# Main.net
KiCad netlist of a schematic drawn in EAGLE
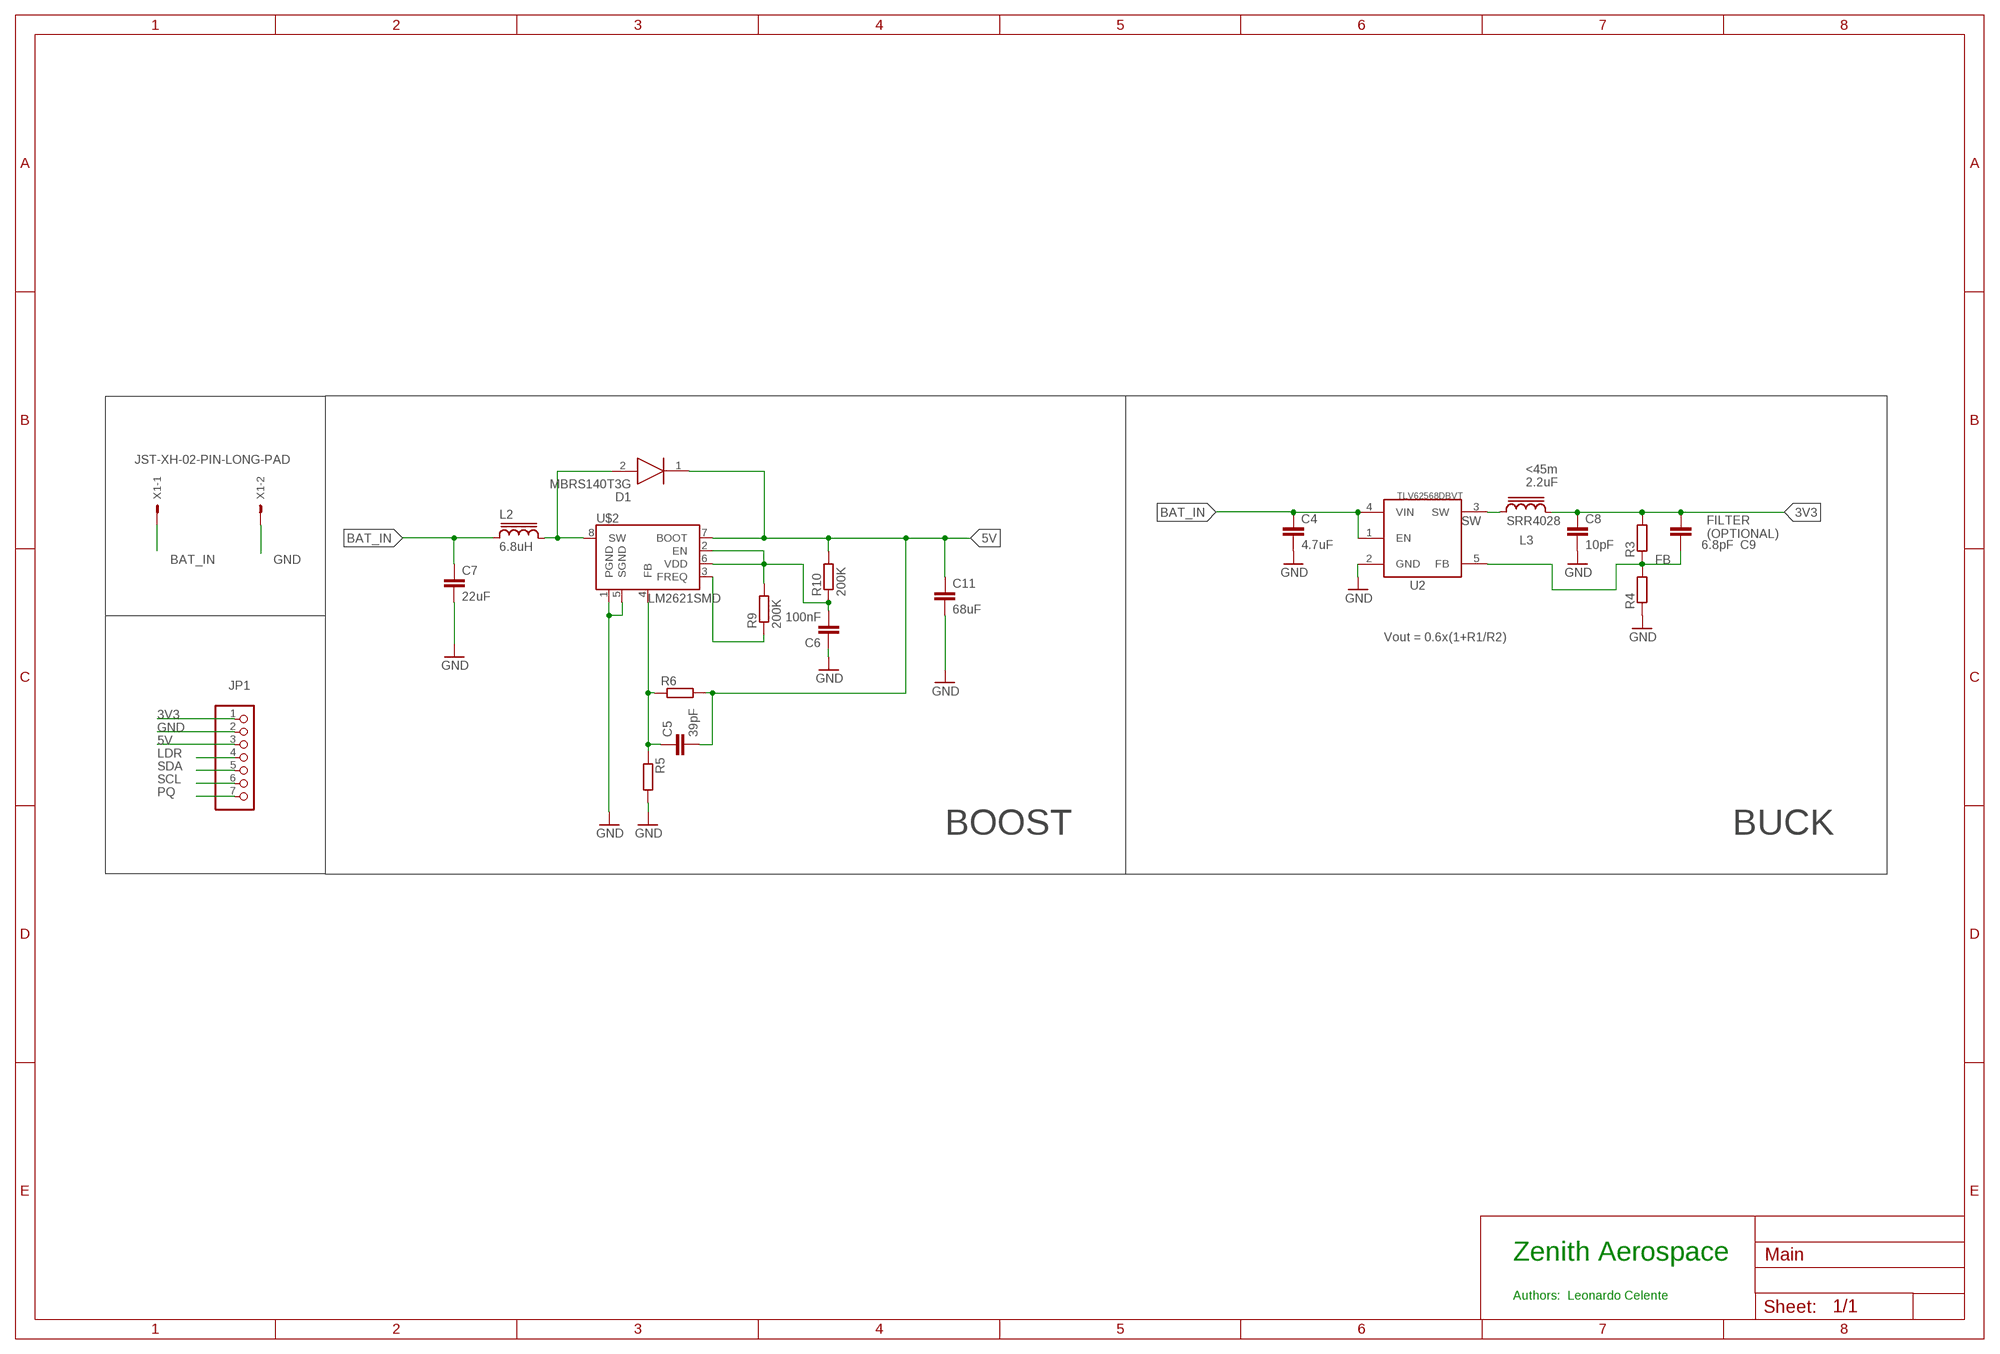
[diagram p0: schematic, sheet 1]

(export (version "E")
  (design (tool "Eeschema 10.0.6"))
  (components
    (comp (ref "C4")
      (value "4.7uF")
      (footprint "eagle-import:C0805")
      (libsource (lib "eagle-import") (part "C-EUC0805"))
    )
    (comp (ref "C5")
      (value "39pF")
      (footprint "eagle-import:C0805")
      (libsource (lib "eagle-import") (part "C-EUC0805"))
    )
    (comp (ref "C6")
      (value "100nF")
      (footprint "eagle-import:C0805")
      (libsource (lib "eagle-import") (part "C-EUC0805"))
    )
    (comp (ref "C7")
      (value "22uF")
      (footprint "eagle-import:C1210")
      (libsource (lib "eagle-import") (part "C-EUC1210"))
    )
    (comp (ref "C8")
      (value "10pF")
      (footprint "eagle-import:C0805")
      (libsource (lib "eagle-import") (part "C-EUC0805"))
    )
    (comp (ref "C9")
      (value "6.8pF")
      (footprint "eagle-import:C0805")
      (libsource (lib "eagle-import") (part "C-EUC0805"))
    )
    (comp (ref "C11")
      (value "68uF")
      (footprint "eagle-import:C1210")
      (libsource (lib "eagle-import") (part "C-EUC1210"))
    )
    (comp (ref "D1")
      (value "MBRS140T3G")
      (footprint "eagle-import:DIOM5436X247N")
      (fields (field (name "RS_PART_NUMBER") "5452074P"))
      (libsource (lib "eagle-import") (part "MBRS140T3G"))
    )
    (comp (ref "JP1")
      (value "PINHD-1X7")
      (footprint "eagle-import:1X07")
      (libsource (lib "eagle-import") (part "PINHD-1X7"))
    )
    (comp (ref "L2")
      (value "6.8uH")
      (footprint "eagle-import:SRR1280")
      (libsource (lib "eagle-import") (part "SRR1280"))
    )
    (comp (ref "L3")
      (value "SRR4028")
      (footprint "eagle-import:SRR4028")
      (fields (field (name "DCR") "<45m") (field (name "L") "2.2uF"))
      (libsource (lib "eagle-import") (part "SRR4028"))
    )
    (comp (ref "R3")
      (value "R-EU_R0805")
      (footprint "eagle-import:R0805")
      (libsource (lib "eagle-import") (part "R-EU_R0805"))
    )
    (comp (ref "R4")
      (value "R-EU_R0805")
      (footprint "eagle-import:R0805")
      (libsource (lib "eagle-import") (part "R-EU_R0805"))
    )
    (comp (ref "R5")
      (value "R-EU_R0805")
      (footprint "eagle-import:R0805")
      (libsource (lib "eagle-import") (part "R-EU_R0805"))
    )
    (comp (ref "R6")
      (value "R-EU_R0805")
      (footprint "eagle-import:R0805")
      (libsource (lib "eagle-import") (part "R-EU_R0805"))
    )
    (comp (ref "R9")
      (value "200K")
      (footprint "eagle-import:R0805")
      (libsource (lib "eagle-import") (part "R-EU_R0805"))
    )
    (comp (ref "R10")
      (value "200K")
      (footprint "eagle-import:R0805")
      (libsource (lib "eagle-import") (part "R-EU_R0805"))
    )
    (comp (ref "U$2")
      (value "LM2621SMD")
      (footprint "eagle-import:MSOP-8")
      (libsource (lib "eagle-import") (part "LM2621SMD"))
    )
    (comp (ref "U2")
      (value "TLV62568DBVT")
      (footprint "eagle-import:SOT95P280X145-5N")
      (libsource (lib "eagle-import") (part "TLV62568DBVT"))
    )
    (comp (ref "X1")
      (value "JST-XH-02-PIN-LONG-PAD")
      (footprint "eagle-import:JST-XH-02-PACKAGE-LONG-PAD")
      (libsource (lib "eagle-import") (part "JST-XH-02-PIN-LONG-PAD"))
    )
  )
  (nets
    (net (code "1") (name "/FB") (class "Default")
      (node (ref "C9") (pin "2") (pinfunction "2_2") (pintype "passive"))
      (node (ref "R3") (pin "1") (pinfunction "1_1") (pintype "passive"))
      (node (ref "R4") (pin "2") (pinfunction "2_2") (pintype "passive"))
      (node (ref "U2") (pin "5") (pinfunction "FB_5") (pintype "input"))
    )
    (net (code "2") (name "/LDR") (class "Default")
      (node (ref "JP1") (pin "4") (pinfunction "4_4") (pintype "passive"))
    )
    (net (code "3") (name "/PQ") (class "Default")
      (node (ref "JP1") (pin "7") (pinfunction "7_7") (pintype "passive"))
    )
    (net (code "4") (name "/SCL") (class "Default")
      (node (ref "JP1") (pin "6") (pinfunction "6_6") (pintype "passive"))
    )
    (net (code "5") (name "/SDA") (class "Default")
      (node (ref "JP1") (pin "5") (pinfunction "5_5") (pintype "passive"))
    )
    (net (code "6") (name "/SW") (class "Default")
      (node (ref "L3") (pin "1") (pinfunction "1_1") (pintype "passive"))
      (node (ref "U2") (pin "3") (pinfunction "SW_3") (pintype "power_in"))
    )
    (net (code "7") (name "3V3") (class "Default")
      (node (ref "C8") (pin "1") (pinfunction "1_1") (pintype "passive"))
      (node (ref "C9") (pin "1") (pinfunction "1_1") (pintype "passive"))
      (node (ref "JP1") (pin "1") (pinfunction "1_1") (pintype "passive"))
      (node (ref "L3") (pin "2") (pinfunction "2_2") (pintype "passive"))
      (node (ref "R3") (pin "2") (pinfunction "2_2") (pintype "passive"))
    )
    (net (code "8") (name "5V") (class "Default")
      (node (ref "C11") (pin "1") (pinfunction "1_1") (pintype "passive"))
      (node (ref "C5") (pin "2") (pinfunction "2_2") (pintype "passive"))
      (node (ref "D1") (pin "1") (pinfunction "K_1") (pintype "bidirectional"))
      (node (ref "JP1") (pin "3") (pinfunction "3_3") (pintype "passive"))
      (node (ref "R10") (pin "2") (pinfunction "2_2") (pintype "passive"))
      (node (ref "R6") (pin "2") (pinfunction "2_2") (pintype "passive"))
      (node (ref "U$2") (pin "7") (pinfunction "BOOT_7") (pintype "bidirectional"))
    )
    (net (code "9") (name "BAT_IN") (class "Default")
      (node (ref "C4") (pin "1") (pinfunction "1_1") (pintype "passive"))
      (node (ref "C7") (pin "1") (pinfunction "1_1") (pintype "passive"))
      (node (ref "L2") (pin "1") (pinfunction "1_1") (pintype "passive"))
      (node (ref "U2") (pin "1") (pinfunction "EN_1") (pintype "input"))
      (node (ref "U2") (pin "4") (pinfunction "VIN_4") (pintype "input"))
      (node (ref "X1") (pin "1") (pinfunction "S_1") (pintype "passive"))
    )
    (net (code "10") (name "GND") (class "Default")
      (node (ref "C11") (pin "2") (pinfunction "2_2") (pintype "passive"))
      (node (ref "C4") (pin "2") (pinfunction "2_2") (pintype "passive"))
      (node (ref "C6") (pin "1") (pinfunction "1_1") (pintype "passive"))
      (node (ref "C7") (pin "2") (pinfunction "2_2") (pintype "passive"))
      (node (ref "C8") (pin "2") (pinfunction "2_2") (pintype "passive"))
      (node (ref "JP1") (pin "2") (pinfunction "2_2") (pintype "passive"))
      (node (ref "R4") (pin "1") (pinfunction "1_1") (pintype "passive"))
      (node (ref "R5") (pin "2") (pinfunction "2_2") (pintype "passive"))
      (node (ref "U$2") (pin "1") (pinfunction "PGND_1") (pintype "bidirectional"))
      (node (ref "U$2") (pin "5") (pinfunction "SGND_5") (pintype "bidirectional"))
      (node (ref "U2") (pin "2") (pinfunction "GND_2") (pintype "power_in"))
      (node (ref "X1") (pin "2") (pinfunction "S_2") (pintype "passive"))
    )
    (net (code "11") (name "Net-(D1-A)") (class "Default")
      (node (ref "D1") (pin "2") (pinfunction "A_2") (pintype "bidirectional"))
      (node (ref "L2") (pin "2") (pinfunction "2_2") (pintype "passive"))
      (node (ref "U$2") (pin "8") (pinfunction "SW_8") (pintype "bidirectional"))
    )
    (net (code "12") (name "Net-(U$2-EN)") (class "Default")
      (node (ref "C6") (pin "2") (pinfunction "2_2") (pintype "passive"))
      (node (ref "R10") (pin "1") (pinfunction "1_1") (pintype "passive"))
      (node (ref "R9") (pin "2") (pinfunction "2_2") (pintype "passive"))
      (node (ref "U$2") (pin "2") (pinfunction "EN_2") (pintype "bidirectional"))
      (node (ref "U$2") (pin "6") (pinfunction "VDD_6") (pintype "bidirectional"))
    )
    (net (code "13") (name "Net-(U$2-FB)") (class "Default")
      (node (ref "C5") (pin "1") (pinfunction "1_1") (pintype "passive"))
      (node (ref "R5") (pin "1") (pinfunction "1_1") (pintype "passive"))
      (node (ref "R6") (pin "1") (pinfunction "1_1") (pintype "passive"))
      (node (ref "U$2") (pin "4") (pinfunction "FB_4") (pintype "bidirectional"))
    )
    (net (code "14") (name "Net-(U$2-FREQ)") (class "Default")
      (node (ref "R9") (pin "1") (pinfunction "1_1") (pintype "passive"))
      (node (ref "U$2") (pin "3") (pinfunction "FREQ_3") (pintype "bidirectional"))
    )
  )
)
